# WX0_011_910DL.net
KiCad netlist of a schematic drawn in Altium Designer
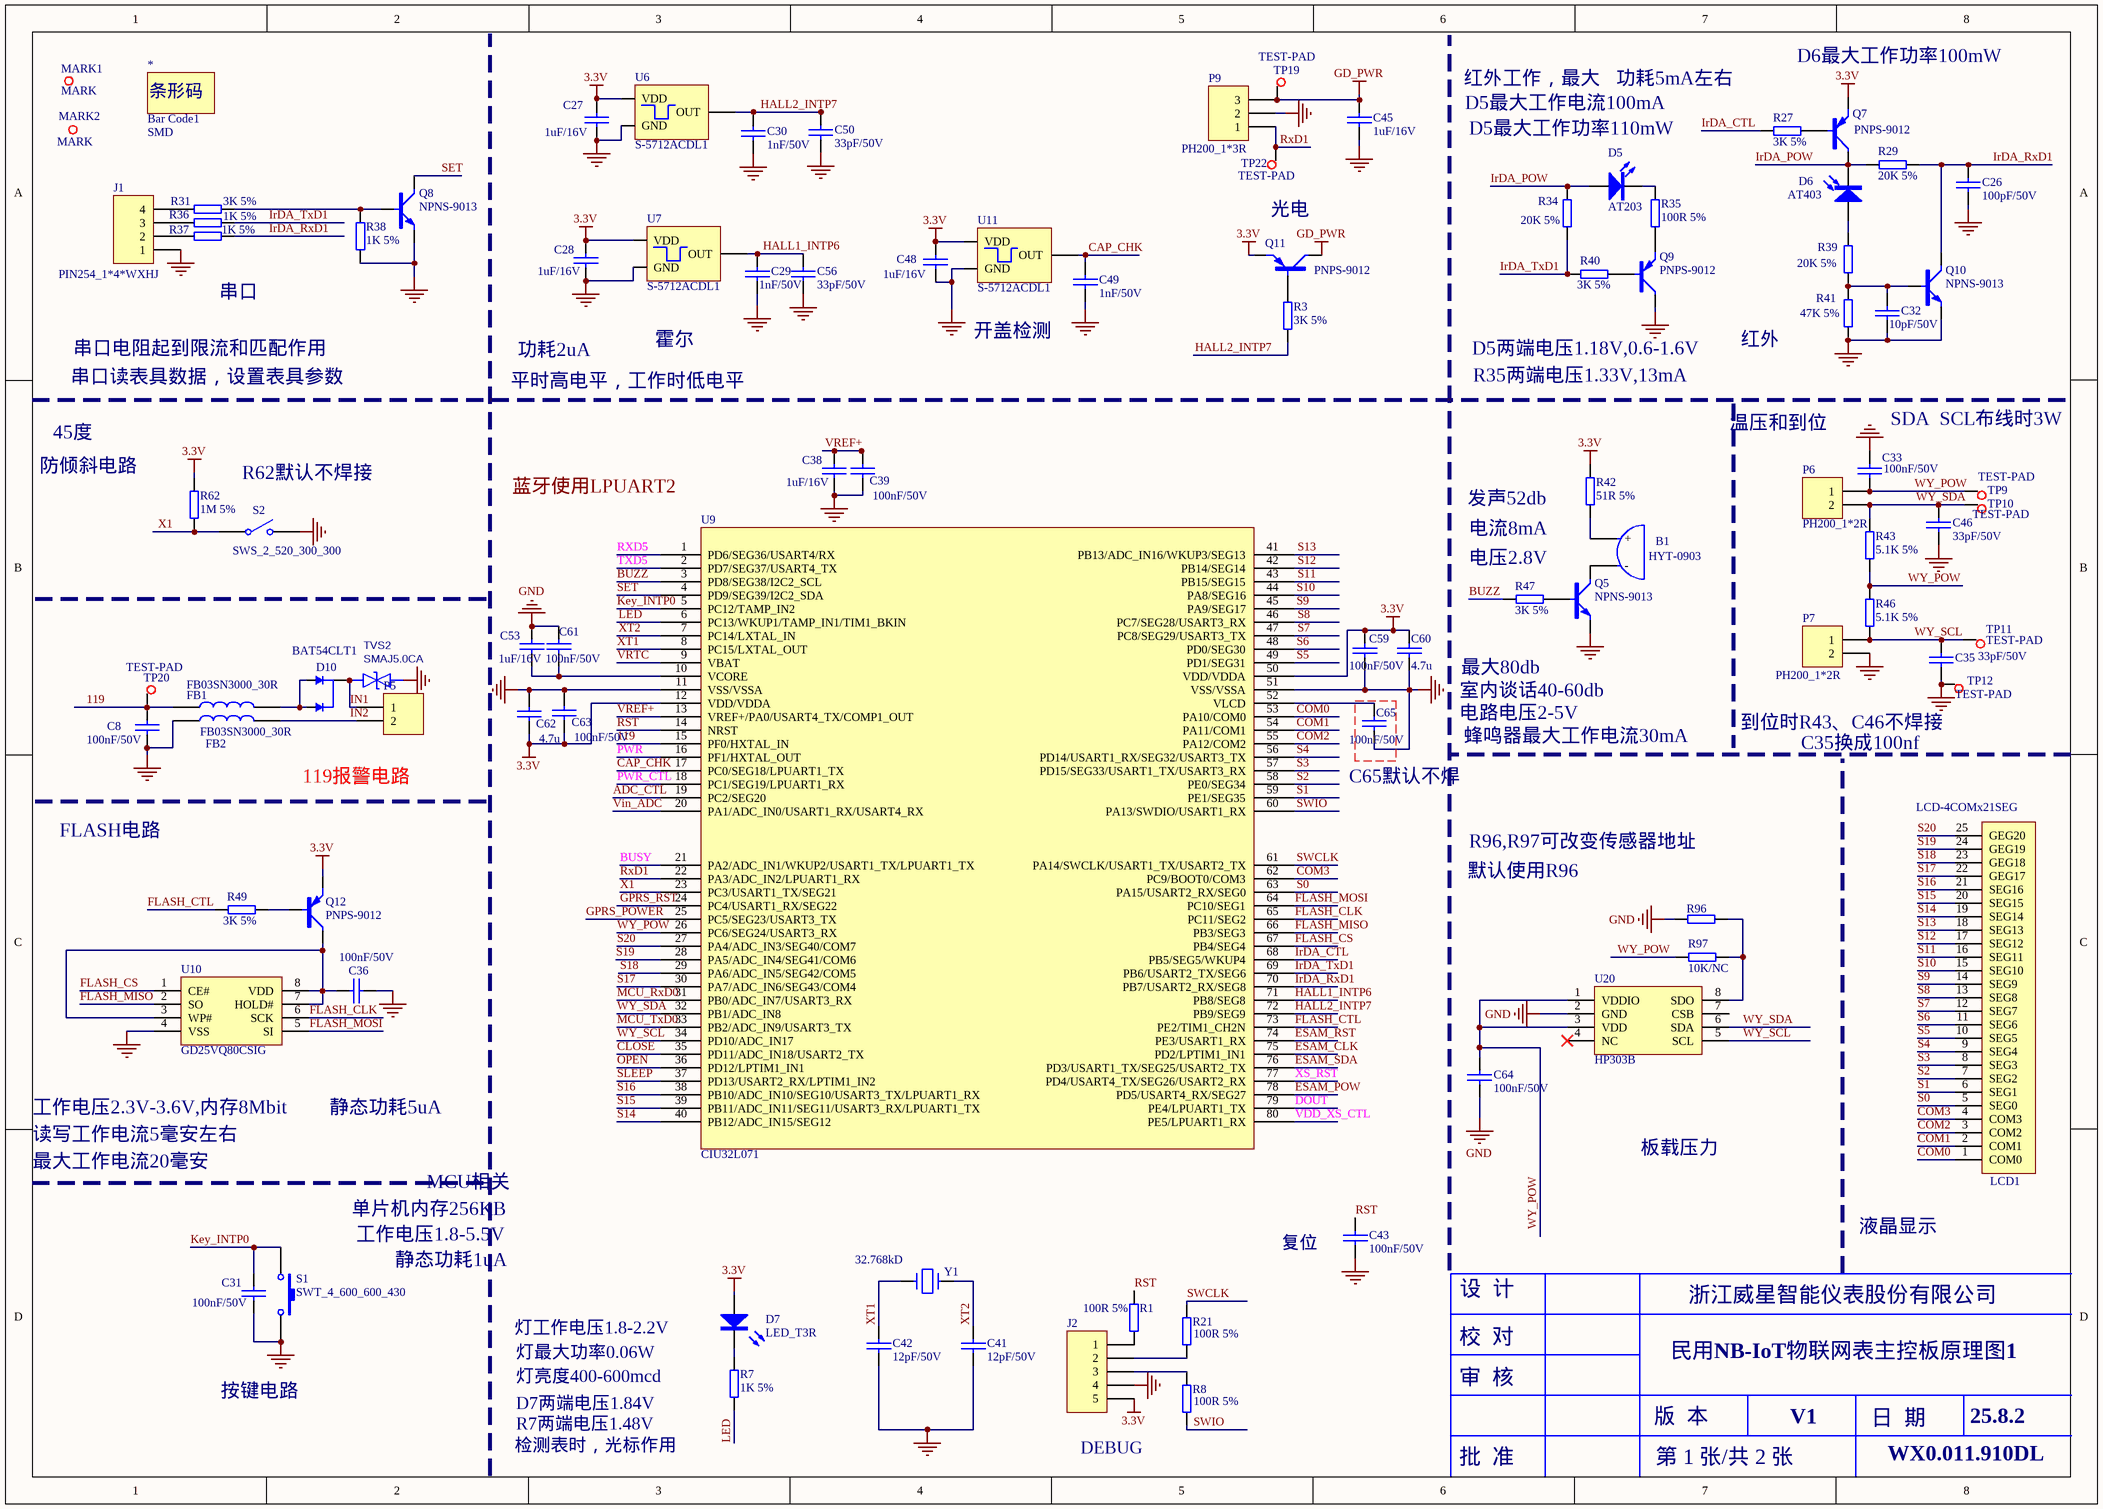
[diagram p0: WX0.011.910DL.SchDoc]

(export (version "E")
  (design (tool "Eeschema 10.0.6"))
  (components
    (comp (ref "*")
      (value "Bar Code1")
      (footprint "Bar Code1")
      (description "条形码 ,填充，无需焊接器件")
      (fields (field (name "PART NUMBER") "AD_WXHJ_Bar Code_02") (field (name "SMD/DIP") "SMD"))
      (libsource (lib "Database_Libs2") (part "05_AD_WXHJ_Bar Code_02"))
    )
    (comp (ref "B1")
      (value "HYT-0903")
      (footprint "HYT-0903")
      (description "直插,直径9mm,高5.5mm,5 V,2 V,30 mA,兴化市华宇电子有限公司,HYT-0903")
      (fields (field (name "PART NUMBER") "1010602-0007"))
      (libsource (lib "Database_Libs2") (part "07_HYT-0903"))
    )
    (comp (ref "C8")
      (value "100nF/50V")
      (footprint "CAP0603")
      (description "104pF,50 V,±10%,0603,国巨,CC0603KRX7R9BB104")
      (fields (field (name "PART NUMBER") "101020103-0021"))
      (libsource (lib "Database_Libs2") (part "CC03K7R9_100N"))
    )
    (comp (ref "C26")
      (value "100pF/50V")
      (footprint "CAP0603")
      (description "101pf,50 V,±5%,0603,国巨,CC0603JRNP09BN101")
      (fields (field (name "PART NUMBER") "101020103-0010"))
      (libsource (lib "Database_Libs2") (part "CC03JPO9_101P"))
    )
    (comp (ref "C27")
      (value "1uF/16V")
      (footprint "CAP0603")
      (description "105pF,16 V,±10%,0603,国巨,CC0603KRX7R7BB105")
      (fields (field (name "PART NUMBER") "101020103-0003"))
      (libsource (lib "Database_Libs2") (part "CC03K7R7_1U"))
    )
    (comp (ref "C28")
      (value "1uF/16V")
      (footprint "CAP0603")
      (description "105pF,16 V,±10%,0603,国巨,CC0603KRX7R7BB105")
      (fields (field (name "PART NUMBER") "101020103-0003"))
      (libsource (lib "Database_Libs2") (part "CC03K7R7_1U"))
    )
    (comp (ref "C29")
      (value "1nF/50V")
      (footprint "CAP0603")
      (description "102pF,50 V,±10%,0603,国巨,CC0603KRX7R9BB102")
      (fields (field (name "PART NUMBER") "101020103-0022"))
      (libsource (lib "Database_Libs2") (part "CC03K7R9_1N"))
    )
    (comp (ref "C30")
      (value "1nF/50V")
      (footprint "CAP0603")
      (description "102pF,50 V,±10%,0603,国巨,CC0603KRX7R9BB102")
      (fields (field (name "PART NUMBER") "101020103-0022"))
      (libsource (lib "Database_Libs2") (part "CC03K7R9_1N"))
    )
    (comp (ref "C31")
      (value "100nF/50V")
      (footprint "CAP0603")
      (description "104pF,50 V,±10%,0603,国巨,CC0603KRX7R9BB104")
      (fields (field (name "PART NUMBER") "101020103-0021"))
      (libsource (lib "Database_Libs2") (part "CC03K7R9_100N"))
    )
    (comp (ref "C32")
      (value "10pF/50V")
      (footprint "CAP0603")
      (description "10pF,50 V,±5%,0603,X7R,国巨,CC0603JRNPO9BN100")
      (fields (field (name "PART NUMBER") "101020103-0014"))
      (libsource (lib "Database_Libs2") (part "CC03JPO9_10P"))
    )
    (comp (ref "C33")
      (value "100nF/50V")
      (footprint "CAP0603")
      (description "104pF,50 V,±10%,0603,国巨,CC0603KRX7R9BB104")
      (fields (field (name "PART NUMBER") "101020103-0021"))
      (libsource (lib "Database_Libs2") (part "CC03K7R9_100N"))
    )
    (comp (ref "C35")
      (value "33pF/50V")
      (footprint "CAP0603")
      (fields (field (name "PART NUMBER") "101020103-0021"))
      (libsource (lib "Database_Libs2") (part "CC03K7R9_100N"))
    )
    (comp (ref "C36")
      (value "100nF/50V")
      (footprint "CAP0603")
      (description "104pF,50 V,±10%,0603,国巨,CC0603KRX7R9BB104")
      (fields (field (name "PART NUMBER") "101020103-0021"))
      (libsource (lib "Database_Libs2") (part "CC03K7R9_100N"))
    )
    (comp (ref "C38")
      (value "1uF/16V")
      (footprint "CAP0603")
      (description "105pF,16 V,±10%,0603,国巨,CC0603KRX7R7BB105")
      (fields (field (name "PART NUMBER") "101020103-0003"))
      (libsource (lib "Database_Libs2") (part "CC03K7R7_1U"))
    )
    (comp (ref "C39")
      (value "100nF/50V")
      (footprint "CAP0603")
      (description "104pF,50 V,±10%,0603,国巨,CC0603KRX7R9BB104")
      (fields (field (name "PART NUMBER") "101020103-0021"))
      (libsource (lib "Database_Libs2") (part "CC03K7R9_100N"))
    )
    (comp (ref "C41")
      (value "12pF/50V")
      (footprint "CAP0603")
      (description "12P,50 V,±5%,0603,国巨,CC0603JRNPO9BN12")
      (fields (field (name "PART NUMBER") "101020103-0005"))
      (libsource (lib "Database_Libs2") (part "CC03JPO9_12P"))
    )
    (comp (ref "C42")
      (value "12pF/50V")
      (footprint "CAP0603")
      (description "12P,50 V,±5%,0603,国巨,CC0603JRNPO9BN12")
      (fields (field (name "PART NUMBER") "101020103-0005"))
      (libsource (lib "Database_Libs2") (part "CC03JPO9_12P"))
    )
    (comp (ref "C43")
      (value "100nF/50V")
      (footprint "CAP0603")
      (description "104pF,50 V,±10%,0603,国巨,CC0603KRX7R9BB104")
      (fields (field (name "PART NUMBER") "101020103-0021"))
      (libsource (lib "Database_Libs2") (part "CC03K7R9_100N"))
    )
    (comp (ref "C45")
      (value "1uF/16V")
      (footprint "CAP0603")
      (description "105pF,16 V,±10%,0603,国巨,CC0603KRX7R7BB105")
      (fields (field (name "PART NUMBER") "101020103-0003"))
      (libsource (lib "Database_Libs2") (part "CC03K7R7_1U"))
    )
    (comp (ref "C46")
      (value "33pF/50V")
      (footprint "CAP0603")
      (description "33pF,50 V,±10%,0603,国巨,CC0603KRNPO9BN33")
      (fields (field (name "PART NUMBER") "101020103-0027"))
      (libsource (lib "Database_Libs2") (part "CC03KPO9_33P"))
    )
    (comp (ref "C48")
      (value "1uF/16V")
      (footprint "CAP0603")
      (description "105pF,16 V,±10%,0603,国巨,CC0603KRX7R7BB105")
      (fields (field (name "PART NUMBER") "101020103-0003"))
      (libsource (lib "Database_Libs2") (part "CC03K7R7_1U"))
    )
    (comp (ref "C49")
      (value "1nF/50V")
      (footprint "CAP0603")
      (description "102pF,50 V,±10%,0603,国巨,CC0603KRX7R9BB102")
      (fields (field (name "PART NUMBER") "101020103-0022"))
      (libsource (lib "Database_Libs2") (part "CC03K7R9_1N"))
    )
    (comp (ref "C50")
      (value "33pF/50V")
      (footprint "CAP0603")
      (description "33pF,50 V,±10%,0603,国巨,CC0603KRNPO9BN33")
      (fields (field (name "PART NUMBER") "101020103-0027"))
      (libsource (lib "Database_Libs2") (part "CC03KPO9_33P"))
    )
    (comp (ref "C53")
      (value "1uF/16V")
      (footprint "CAP0603")
      (description "105pF,16 V,±10%,0603,国巨,CC0603KRX7R7BB105")
      (fields (field (name "PART NUMBER") "101020103-0003"))
      (libsource (lib "Database_Libs2") (part "CC03K7R7_1U"))
    )
    (comp (ref "C56")
      (value "33pF/50V")
      (footprint "CAP0603")
      (description "33pF,50 V,±10%,0603,国巨,CC0603KRNPO9BN33")
      (fields (field (name "PART NUMBER") "101020103-0027"))
      (libsource (lib "Database_Libs2") (part "CC03KPO9_33P"))
    )
    (comp (ref "C59")
      (value "100nF/50V")
      (footprint "CAP0603")
      (description "104pF,50 V,±10%,0603,国巨,CC0603KRX7R9BB104")
      (fields (field (name "PART NUMBER") "101020103-0021"))
      (libsource (lib "Database_Libs2") (part "CC03K7R9_100N"))
    )
    (comp (ref "C60")
      (value "4.7u")
      (footprint "CAP0603")
      (description "104pF,50 V,±10%,0603,国巨,CC0603KRX7R9BB104")
      (fields (field (name "PART NUMBER") "101020103-0021"))
      (libsource (lib "Database_Libs2") (part "CC03K7R9_100N"))
    )
    (comp (ref "C61")
      (value "100nF/50V")
      (footprint "CAP0603")
      (description "104pF,50 V,±10%,0603,国巨,CC0603KRX7R9BB104")
      (fields (field (name "PART NUMBER") "101020103-0021"))
      (libsource (lib "Database_Libs2") (part "CC03K7R9_100N"))
    )
    (comp (ref "C62")
      (value "4.7u")
      (footprint "CAP0603")
      (description "104pF,50 V,±10%,0603,国巨,CC0603KRX7R9BB104")
      (fields (field (name "PART NUMBER") "101020103-0021"))
      (libsource (lib "Database_Libs2") (part "CC03K7R9_100N"))
    )
    (comp (ref "C63")
      (value "100nF/50V")
      (footprint "CAP0603")
      (description "104pF,50 V,±10%,0603,国巨,CC0603KRX7R9BB104")
      (fields (field (name "PART NUMBER") "101020103-0021"))
      (libsource (lib "Database_Libs2") (part "CC03K7R9_100N"))
    )
    (comp (ref "C64")
      (value "100nF/50V")
      (footprint "CAP0603")
      (description "104pF,50 V,±10%,0603,国巨,CC0603KRX7R9BB104")
      (fields (field (name "PART NUMBER") "101020103-0021"))
      (libsource (lib "Database_Libs2") (part "CC03K7R9_100N"))
    )
    (comp (ref "C65")
      (value "100nF/50V")
      (footprint "CAP0603")
      (description "104pF,50 V,±10%,0603,国巨,CC0603KRX7R9BB104")
      (fields (field (name "PART NUMBER") "101020103-0021"))
      (libsource (lib "Database_Libs2") (part "CC03K7R9_100N"))
    )
    (comp (ref "D5")
      (value "AT203")
      (footprint "IR_254_532_300")
      (description "DIP-2,φ3,插件,红光,上海品观电子有限公司/可得,AT203")
      (fields (field (name "PART NUMBER") "101040102-0010"))
      (libsource (lib "Database_Libs2") (part "01_AT203"))
    )
    (comp (ref "D6")
      (value "AT403")
      (footprint "IR_254_532_300")
      (description "DIP-2,φ3,插件,红光,上海品观电子有限公司/可得,AT403-PD-01")
      (fields (field (name "PART NUMBER") "101040102-0011"))
      (libsource (lib "Database_Libs2") (part "01_AT403"))
    )
    (comp (ref "D7")
      (value "LED_T3R")
      (footprint "LED2_300")
      (description "圆形插件,3mm 圆形,插件,红光,湖北匡通电子有限公司,3BB4HC")
      (fields (field (name "PART NUMBER") "101040102-0001"))
      (libsource (lib "Database_Libs2") (part "01-LED_T3R"))
    )
    (comp (ref "D10")
      (value "BAT54CLT1")
      (footprint "SOT-23")
      (description "BAT54CLT1，SOT23-3,SOT23-3,0.2 A,0.8 V,30 V,安森美,BAT54CLT1")
      (fields (field (name "PART NUMBER") "101040101-0038"))
      (libsource (lib "Database_Libs2") (part "02_BAT54CLT1"))
    )
    (comp (ref "FB1")
      (value "FB03SN3000_30R")
      (footprint "IND0603")
      (description "chilisin(奇力新),0603,30Ω ±25% @100MHz,150 V,125 ℃,PBY160808T-300Y-N,-55 ℃,不含铅,,,圆盘,30Ω ±25% @100MHz")
      (fields (field (name "PART NUMBER") "109010101-0003"))
      (libsource (lib "Database_Libs2") (part "06_FB03SN3000_30R"))
    )
    (comp (ref "FB2")
      (value "FB03SN3000_30R")
      (footprint "IND0603")
      (description "chilisin(奇力新),0603,30Ω ±25% @100MHz,150 V,125 ℃,PBY160808T-300Y-N,-55 ℃,不含铅,,,圆盘,30Ω ±25% @100MHz")
      (fields (field (name "PART NUMBER") "109010101-0003"))
      (libsource (lib "Database_Libs2") (part "06_FB03SN3000_30R"))
    )
    (comp (ref "J1")
      (value "PIN254_1*4*WXHJ")
      (footprint "PIN254_1*4*WXHJ")
      (description "1*4 ，Φ1.0 ，2.54mm，直脚,无需焊接器件")
      (fields (field (name "PART NUMBER") "AD_WXHJ_PinHeader_01"))
      (libsource (lib "Database_Libs2") (part "PIN254_1*4*WXHJ"))
    )
    (comp (ref "J2")
      (value "PIN254_1*5*WXHJ")
      (footprint "PIN254_1*5*1100S")
      (description "1*5 ，Φ1.0 ，2.54mm，直脚,无需焊接器件")
      (fields (field (name "PART NUMBER") "AD_WXHJ_PinHeader_02"))
      (libsource (lib "Database_Libs2") (part "PIN254_1*5*WXHJ"))
    )
    (comp (ref "LCD1")
      (value "GVH21861A-HPP")
      (footprint "LCD_GVH21861A-HPP")
      (fields (field (name "PART NUMBER") "1010801-0028") (field (name "SMD/DIP") "LCD-4COMx21SEG"))
      (libsource (lib "Database_Libs2") (part "03_LCD_GVH21861A-HPP"))
    )
    (comp (ref "MARK1")
      (value "MARK")
      (footprint "MARK")
      (description "MARK点")
      (fields (field (name "PART NUMBER") "AD_WXHJ_MARK_01"))
      (libsource (lib "Database_Libs2") (part "MARK"))
    )
    (comp (ref "MARK2")
      (value "MARK")
      (footprint "MARK")
      (description "MARK点")
      (fields (field (name "PART NUMBER") "AD_WXHJ_MARK_01"))
      (libsource (lib "Database_Libs2") (part "MARK"))
    )
    (comp (ref "P5")
      (value "~")
      (footprint "WXHJ_Connect_01")
      (description "电源连接线")
      (fields (field (name "PART NUMBER") "AD_WXHJ_Connect_01"))
      (libsource (lib "Database_Libs2") (part "WXHJ_Connect_01"))
    )
    (comp (ref "P6")
      (value "PH200_1*2R")
      (footprint "PH200_1*2R")
      (description "2.0-2AW,直插弯座，2PIN，脚间距2mm，带防翘起,公头,单排,2.0-2AW;直插弯座，2PIN,脚间距2mm，带防翘起")
      (fields (field (name "PART NUMBER") "1010902-0105"))
      (libsource (lib "Database_Libs2") (part "PH200_1*2R"))
    )
    (comp (ref "P7")
      (value "PH200_1*2R")
      (footprint "PH200_1*2R")
      (description "2.0-2AW,直插弯座，2PIN，脚间距2mm，带防翘起,公头,单排,2.0-2AW;直插弯座，2PIN,脚间距2mm，带防翘起")
      (fields (field (name "PART NUMBER") "1010902-0105"))
      (libsource (lib "Database_Libs2") (part "PH200_1*2R"))
    )
    (comp (ref "P9")
      (value "PH200_1*3R")
      (footprint "PH200_1*3R")
      (description "2.0-3AW,3PIN，2mm脚间距,公头,单排,2.0-3AW；3PIN，脚间距2mm直插弯座带防翘起")
      (fields (field (name "PART NUMBER") "1010902-0104"))
      (libsource (lib "Database_Libs2") (part "PH200_1*3R"))
    )
    (comp (ref "Q5")
      (value "NPNS-9013")
      (footprint "SOT-23")
      (description "9013,NPN,SOT-23,长电,S9013")
      (fields (field (name "PART NUMBER") "101040201-0002"))
      (libsource (lib "Database_Libs2") (part "03_NPNS-9013"))
    )
    (comp (ref "Q7")
      (value "PNPS-9012")
      (footprint "SOT-23")
      (description "9012,PNP,SOT-23,JCET;长电,S9012")
      (fields (field (name "PART NUMBER") "101040201-0001"))
      (libsource (lib "Database_Libs2") (part "03_PNPS-9012"))
    )
    (comp (ref "Q8")
      (value "NPNS-9013")
      (footprint "SOT-23")
      (description "9013,NPN,SOT-23,长电,S9013")
      (fields (field (name "PART NUMBER") "101040201-0002"))
      (libsource (lib "Database_Libs2") (part "03_NPNS-9013"))
    )
    (comp (ref "Q9")
      (value "PNPS-9012")
      (footprint "SOT-23")
      (description "9012,PNP,SOT-23,JCET;长电,S9012")
      (fields (field (name "PART NUMBER") "101040201-0001"))
      (libsource (lib "Database_Libs2") (part "03_PNPS-9012"))
    )
    (comp (ref "Q10")
      (value "NPNS-9013")
      (footprint "SOT-23")
      (description "9013,NPN,SOT-23,长电,S9013")
      (fields (field (name "PART NUMBER") "101040201-0002"))
      (libsource (lib "Database_Libs2") (part "03_NPNS-9013"))
    )
    (comp (ref "Q11")
      (value "PNPS-9012")
      (footprint "SOT-23")
      (description "9012,PNP,SOT-23,JCET;长电,S9012")
      (fields (field (name "PART NUMBER") "101040201-0001"))
      (libsource (lib "Database_Libs2") (part "03_PNPS-9012"))
    )
    (comp (ref "Q12")
      (value "PNPS-9012")
      (footprint "SOT-23")
      (description "9012,PNP,SOT-23,JCET;长电,S9012")
      (fields (field (name "PART NUMBER") "101040201-0001"))
      (libsource (lib "Database_Libs2") (part "03_PNPS-9012"))
    )
    (comp (ref "R1")
      (value "100R 5%")
      (footprint "RES0603")
      (description "100R,±5%,1/10W,0603,国巨,RC0603JR-07100RL")
      (fields (field (name "PART NUMBER") "101010103-0022"))
      (libsource (lib "Database_Libs2") (part "RC03J_100R"))
    )
    (comp (ref "R3")
      (value "3K 5%")
      (footprint "RES0603")
      (description "国巨,±5%,0603,,155 ℃,-55 ℃,RC0603JR-073KL,无铅,100 ppm/℃,1/10W,,3K")
      (fields (field (name "PART NUMBER") "101010103-0006"))
      (libsource (lib "Database_Libs2") (part "RC03J_3K"))
    )
    (comp (ref "R7")
      (value "1K 5%")
      (footprint "RES0603")
      (description "1K,±5%,1/10W,0603,国巨,RC0603JR-071KL")
      (fields (field (name "PART NUMBER") "101010103-0008"))
      (libsource (lib "Database_Libs2") (part "RC03J_1K"))
    )
    (comp (ref "R8")
      (value "100R 5%")
      (footprint "RES0603")
      (description "100R,±5%,1/10W,0603,国巨,RC0603JR-07100RL")
      (fields (field (name "PART NUMBER") "101010103-0022"))
      (libsource (lib "Database_Libs2") (part "RC03J_100R"))
    )
    (comp (ref "R21")
      (value "100R 5%")
      (footprint "RES0603")
      (description "100R,±5%,1/10W,0603,国巨,RC0603JR-07100RL")
      (fields (field (name "PART NUMBER") "101010103-0022"))
      (libsource (lib "Database_Libs2") (part "RC03J_100R"))
    )
    (comp (ref "R27")
      (value "3K 5%")
      (footprint "RES0603")
      (description "国巨,±5%,0603,,155 ℃,-55 ℃,RC0603JR-073KL,无铅,100 ppm/℃,1/10W,,3K")
      (fields (field (name "PART NUMBER") "101010103-0006"))
      (libsource (lib "Database_Libs2") (part "RC03J_3K"))
    )
    (comp (ref "R29")
      (value "20K 5%")
      (footprint "RES0603")
      (description "国巨,±5%,0603,,155 ℃,-55 ℃,RC0603JR-0720KL,无铅,200 ppm/℃,1/10W,,20K")
      (fields (field (name "PART NUMBER") "101010103-0004"))
      (libsource (lib "Database_Libs2") (part "RC03J_20K"))
    )
    (comp (ref "R31")
      (value "3K 5%")
      (footprint "RES0603")
      (description "国巨,±5%,0603,,155 ℃,-55 ℃,RC0603JR-073KL,无铅,100 ppm/℃,1/10W,,3K")
      (fields (field (name "PART NUMBER") "101010103-0006"))
      (libsource (lib "Database_Libs2") (part "RC03J_3K"))
    )
    (comp (ref "R34")
      (value "20K 5%")
      (footprint "RES0603")
      (description "国巨,±5%,0603,,155 ℃,-55 ℃,RC0603JR-0720KL,无铅,200 ppm/℃,1/10W,,20K")
      (fields (field (name "PART NUMBER") "101010103-0004"))
      (libsource (lib "Database_Libs2") (part "RC03J_20K"))
    )
    (comp (ref "R35")
      (value "100R 5%")
      (footprint "RES0603")
      (description "100R,±5%,1/10W,0603,国巨,RC0603JR-07100RL")
      (fields (field (name "PART NUMBER") "101010103-0022"))
      (libsource (lib "Database_Libs2") (part "RC03J_100R"))
    )
    (comp (ref "R36")
      (value "1K 5%")
      (footprint "RES0603")
      (description "1K,±5%,1/10W,0603,国巨,RC0603JR-071KL")
      (fields (field (name "PART NUMBER") "101010103-0008"))
      (libsource (lib "Database_Libs2") (part "RC03J_1K"))
    )
    (comp (ref "R37")
      (value "1K 5%")
      (footprint "RES0603")
      (description "1K,±5%,1/10W,0603,国巨,RC0603JR-071KL")
      (fields (field (name "PART NUMBER") "101010103-0008"))
      (libsource (lib "Database_Libs2") (part "RC03J_1K"))
    )
    (comp (ref "R38")
      (value "1K 5%")
      (footprint "RES0603")
      (description "1K,±5%,1/10W,0603,国巨,RC0603JR-071KL")
      (fields (field (name "PART NUMBER") "101010103-0008"))
      (libsource (lib "Database_Libs2") (part "RC03J_1K"))
    )
    (comp (ref "R39")
      (value "20K 5%")
      (footprint "RES0603")
      (description "国巨,±5%,0603,,155 ℃,-55 ℃,RC0603JR-0720KL,无铅,200 ppm/℃,1/10W,,20K")
      (fields (field (name "PART NUMBER") "101010103-0004"))
      (libsource (lib "Database_Libs2") (part "RC03J_20K"))
    )
    (comp (ref "R40")
      (value "3K 5%")
      (footprint "RES0603")
      (description "国巨,±5%,0603,,155 ℃,-55 ℃,RC0603JR-073KL,无铅,100 ppm/℃,1/10W,,3K")
      (fields (field (name "PART NUMBER") "101010103-0006"))
      (libsource (lib "Database_Libs2") (part "RC03J_3K"))
    )
    (comp (ref "R41")
      (value "47K 5%")
      (footprint "RES0603")
      (description "47K,±5%,1/10W,0603,国巨,RC0603JR-0747KL")
      (fields (field (name "PART NUMBER") "101010103-0012"))
      (libsource (lib "Database_Libs2") (part "RC03J_47K"))
    )
    (comp (ref "R42")
      (value "51R 5%")
      (footprint "RES0603")
      (description "国巨,±5%,0603,,155 ℃,-55 ℃,RC0603JR-0751RL,无铅,100 ppm/℃,1/10W,,51欧")
      (fields (field (name "PART NUMBER") "101010103-0037"))
      (libsource (lib "Database_Libs2") (part "RC03J_51R"))
    )
    (comp (ref "R43")
      (value "5.1K 5%")
      (footprint "RES0603")
      (description "国巨,±5%,0603,,155 ℃,55 ℃,RC0603JR-075.1KL,无铅,200 ppm/℃,1/10W,,5.1k")
      (fields (field (name "PART NUMBER") "101010103-0015"))
      (libsource (lib "Database_Libs2") (part "RC03J_5.1K"))
    )
    (comp (ref "R46")
      (value "5.1K 5%")
      (footprint "RES0603")
      (description "国巨,±5%,0603,,155 ℃,55 ℃,RC0603JR-075.1KL,无铅,200 ppm/℃,1/10W,,5.1k")
      (fields (field (name "PART NUMBER") "101010103-0015"))
      (libsource (lib "Database_Libs2") (part "RC03J_5.1K"))
    )
    (comp (ref "R47")
      (value "3K 5%")
      (footprint "RES0603")
      (description "国巨,±5%,0603,,155 ℃,-55 ℃,RC0603JR-073KL,无铅,100 ppm/℃,1/10W,,3K")
      (fields (field (name "PART NUMBER") "101010103-0006"))
      (libsource (lib "Database_Libs2") (part "RC03J_3K"))
    )
    (comp (ref "R49")
      (value "3K 5%")
      (footprint "RES0603")
      (description "国巨,±5%,0603,,155 ℃,-55 ℃,RC0603JR-073KL,无铅,100 ppm/℃,1/10W,,3K")
      (fields (field (name "PART NUMBER") "101010103-0006"))
      (libsource (lib "Database_Libs2") (part "RC03J_3K"))
    )
    (comp (ref "R62")
      (value "1M 5%")
      (footprint "RES0603")
      (description "国巨,±5%,0603,,155 ℃,-55 ℃,RC0603JR-071ML,无铅,200 ppm/℃,1/10W,,1M")
      (fields (field (name "PART NUMBER") "101010103-0002"))
      (libsource (lib "Database_Libs2") (part "RC03J_1M"))
    )
    (comp (ref "R96")
      (value "0R 5%")
      (footprint "RES0603")
      (description "国巨,±5%,0603,,155 ℃,-55 ℃,RC0603J2-070RL,无铅,200 ppm/℃,1/10W,,0R")
      (fields (field (name "PART NUMBER") "101010103-0001"))
      (libsource (lib "Database_Libs2") (part "RC03J_0R"))
    )
    (comp (ref "R97")
      (value "10K/NC")
      (footprint "RES0603")
      (description "国巨,±5%,0603,,155 ℃,-55 ℃,RC0603JR-071ML,无铅,200 ppm/℃,1/10W,,1M")
      (libsource (lib "Database_Libs2") (part "RC03J_1M"))
    )
    (comp (ref "S1")
      (value "SWT_4_600_600_430")
      (footprint "SWT_4_600_600")
      (description "TS-1102,机械轻触,6*6*4.3直插,6*6*4.3直插,乐清市羽欧电子")
      (fields (field (name "PART NUMBER") "1011001-0027"))
      (libsource (lib "Database_Libs2") (part "07_SWT_4_600_600_430"))
    )
    (comp (ref "S2")
      (value "SWS_2_520_300_300")
      (footprint "SWS_2_520_300")
      (description "CSX-SEN-645B,垂直45°开关转换,3*5.2mm,360°任意方位倾斜检测,深圳市成晟科技有限公司")
      (fields (field (name "PART NUMBER") "1011001-0051"))
      (libsource (lib "Database_Libs2") (part "07_SWS_2_520_300_300"))
    )
    (comp (ref "TP9")
      (value "TEST-PAD")
      (footprint "TEST-PAD")
      (description "单面焊盘测试点")
      (fields (field (name "PART NUMBER") "AD_WXHJ_TEST-PAD_01"))
      (libsource (lib "Database_Libs2") (part "TEST-PAD"))
    )
    (comp (ref "TP10")
      (value "TEST-PAD")
      (footprint "TEST-PAD")
      (description "单面焊盘测试点")
      (fields (field (name "PART NUMBER") "AD_WXHJ_TEST-PAD_01"))
      (libsource (lib "Database_Libs2") (part "TEST-PAD"))
    )
    (comp (ref "TP11")
      (value "TEST-PAD")
      (footprint "TEST-PAD")
      (description "单面焊盘测试点")
      (fields (field (name "PART NUMBER") "AD_WXHJ_TEST-PAD_01"))
      (libsource (lib "Database_Libs2") (part "TEST-PAD"))
    )
    (comp (ref "TP12")
      (value "TEST-PAD")
      (footprint "TEST-PAD")
      (description "单面焊盘测试点")
      (fields (field (name "PART NUMBER") "AD_WXHJ_TEST-PAD_01"))
      (libsource (lib "Database_Libs2") (part "TEST-PAD"))
    )
    (comp (ref "TP19")
      (value "TEST-PAD")
      (footprint "TEST-PAD")
      (description "单面焊盘测试点")
      (fields (field (name "PART NUMBER") "AD_WXHJ_TEST-PAD_01"))
      (libsource (lib "Database_Libs2") (part "TEST-PAD"))
    )
    (comp (ref "TP20")
      (value "TEST-PAD")
      (footprint "TEST-PAD")
      (description "单面焊盘测试点")
      (fields (field (name "PART NUMBER") "AD_WXHJ_TEST-PAD_01"))
      (libsource (lib "Database_Libs2") (part "TEST-PAD"))
    )
    (comp (ref "TP22")
      (value "TEST-PAD")
      (footprint "TEST-PAD")
      (description "单面焊盘测试点")
      (fields (field (name "PART NUMBER") "AD_WXHJ_TEST-PAD_01"))
      (libsource (lib "Database_Libs2") (part "TEST-PAD"))
    )
    (comp (ref "TVS2")
      (value "SMAJ5.0CA")
      (footprint "SMAJ5.0CA")
      (fields (field (name "BOM_SUPPLIER PART") "C693487") (field (name "CONTRIBUTOR") "LCSC"))
      (libsource (lib "Discrete_WX") (part "SMAJ5.0CA_C693487"))
    )
    (comp (ref "U6")
      (value "S-5712ACDL1")
      (footprint "SOT-23")
      (description "S-5712ACDL1,SOT23-3,3.5 V,1.6 V,2 uA,精工电子,S-5712ACDL1")
      (fields (field (name "PART NUMBER") "1010504-0002"))
      (libsource (lib "Database_Libs2") (part "01_S-5712ACDL1"))
    )
    (comp (ref "U7")
      (value "S-5712ACDL1")
      (footprint "SOT-23")
      (description "S-5712ACDL1,SOT23-3,3.5 V,1.6 V,2 uA,精工电子,S-5712ACDL1")
      (fields (field (name "PART NUMBER") "1010504-0002"))
      (libsource (lib "Database_Libs2") (part "01_S-5712ACDL1"))
    )
    (comp (ref "U9") (value "CIU32L071") (libsource (lib "1111") (part "CIU32L061")))
    (comp (ref "U10") (value "GD25VQ80CSIG") (libsource (lib "Chip_WX") (part "04_GD25VQ80CSIG")))
    (comp (ref "U11")
      (value "S-5712ACDL1")
      (footprint "SOT-23")
      (description "S-5712ACDL1,SOT23-3,3.5 V,1.6 V,2 uA,精工电子,S-5712ACDL1")
      (fields (field (name "PART NUMBER") "1010504-0002"))
      (libsource (lib "Database_Libs2") (part "01_S-5712ACDL1"))
    )
    (comp (ref "U20")
      (value "HP303B")
      (footprint "LGA_8")
      (fields (field (name "PART NUMBER") "1011301-0022"))
      (libsource (lib "Schlib2") (part "HP303B"))
    )
    (comp (ref "Y1")
      (value "32.768kD")
      (footprint "SMD-3215_2P")
      (fields (field (name "PART NUMBER") "1010601-0020"))
      (libsource (lib "Database_Libs2") (part "04_XTALSG12MD_32.768kD"))
    )
  )
  (nets
    (net (code "1") (name "/119") (class "Default")
      (node (ref "C8") (pin "1") (pinfunction "1_1") (pintype "passive"))
      (node (ref "FB1") (pin "1") (pinfunction "1_1") (pintype "passive"))
      (node (ref "TP20") (pin "1") (pinfunction "1_1") (pintype "passive"))
      (node (ref "U9") (pin "15") (pinfunction "PF0/HXTAL_IN_15") (pintype "passive"))
    )
    (net (code "2") (name "/ADC_CTL") (class "Default")
      (node (ref "U9") (pin "19") (pinfunction "PC2/SEG20_19") (pintype "passive"))
    )
    (net (code "3") (name "/BUSY") (class "Default")
      (node (ref "U9") (pin "21") (pinfunction "PA2/ADC_IN1/WKUP2/USART1_TX/LPUART1_TX_21") (pintype "passive"))
    )
    (net (code "4") (name "/BUZZ") (class "Default")
      (node (ref "R47") (pin "1") (pinfunction "1_1") (pintype "passive"))
      (node (ref "U9") (pin "3") (pinfunction "PD8/SEG38/I2C2_SCL_3") (pintype "passive"))
    )
    (net (code "5") (name "/CAP_CHK") (class "Default")
      (node (ref "C49") (pin "1") (pinfunction "1_1") (pintype "passive"))
      (node (ref "U11") (pin "2") (pinfunction "OUT_2") (pintype "passive"))
      (node (ref "U9") (pin "17") (pinfunction "PC0/SEG18/LPUART1_TX_17") (pintype "passive"))
    )
    (net (code "6") (name "/CLOSE") (class "Default")
      (node (ref "U9") (pin "35") (pinfunction "PD11/ADC_IN18/USART2_TX_35") (pintype "passive"))
    )
    (net (code "7") (name "/COM0") (class "Default")
      (node (ref "LCD1") (pin "1") (pinfunction "COM0_1") (pintype "passive"))
      (node (ref "U9") (pin "53") (pinfunction "PA10/COM0_53") (pintype "passive"))
    )
    (net (code "8") (name "/COM1") (class "Default")
      (node (ref "LCD1") (pin "2") (pinfunction "COM1_2") (pintype "passive"))
      (node (ref "U9") (pin "54") (pinfunction "PA11/COM1_54") (pintype "passive"))
    )
    (net (code "9") (name "/COM2") (class "Default")
      (node (ref "LCD1") (pin "3") (pinfunction "COM2_3") (pintype "passive"))
      (node (ref "U9") (pin "55") (pinfunction "PA12/COM2_55") (pintype "passive"))
    )
    (net (code "10") (name "/COM3") (class "Default")
      (node (ref "LCD1") (pin "4") (pinfunction "COM3_4") (pintype "passive"))
      (node (ref "U9") (pin "62") (pinfunction "PC9/BOOT0/COM3_62") (pintype "passive"))
    )
    (net (code "11") (name "/DOUT") (class "Default")
      (node (ref "U9") (pin "79") (pinfunction "PE4/LPUART1_TX_79") (pintype "passive"))
    )
    (net (code "12") (name "/ESAM_CLK") (class "Default")
      (node (ref "U9") (pin "75") (pinfunction "PD2/LPTIM1_IN1_75") (pintype "passive"))
    )
    (net (code "13") (name "/ESAM_POW") (class "Default")
      (node (ref "U9") (pin "78") (pinfunction "PD5/USART4_RX/SEG27_78") (pintype "passive"))
    )
    (net (code "14") (name "/ESAM_RST") (class "Default")
      (node (ref "U9") (pin "74") (pinfunction "PE3/USART1_RX_74") (pintype "passive"))
    )
    (net (code "15") (name "/ESAM_SDA") (class "Default")
      (node (ref "U9") (pin "76") (pinfunction "PD3/USART1_TX/SEG25/USART2_TX_76") (pintype "passive"))
    )
    (net (code "16") (name "/FLASH_CLK") (class "Default")
      (node (ref "U10") (pin "6") (pinfunction "SCK_6") (pintype "passive"))
      (node (ref "U9") (pin "65") (pinfunction "PC11/SEG2_65") (pintype "passive"))
    )
    (net (code "17") (name "/FLASH_CS") (class "Default")
      (node (ref "U10") (pin "1") (pinfunction "CE#_1") (pintype "passive"))
      (node (ref "U9") (pin "67") (pinfunction "PB4/SEG4_67") (pintype "passive"))
    )
    (net (code "18") (name "/FLASH_CTL") (class "Default")
      (node (ref "R49") (pin "1") (pinfunction "1_1") (pintype "passive"))
      (node (ref "U9") (pin "73") (pinfunction "PE2/TIM1_CH2N_73") (pintype "passive"))
    )
    (net (code "19") (name "/FLASH_MISO") (class "Default")
      (node (ref "U10") (pin "2") (pinfunction "SO_2") (pintype "passive"))
      (node (ref "U9") (pin "66") (pinfunction "PB3/SEG3_66") (pintype "passive"))
    )
    (net (code "20") (name "/FLASH_MOSI") (class "Default")
      (node (ref "U10") (pin "5") (pinfunction "SI_5") (pintype "passive"))
      (node (ref "U9") (pin "64") (pinfunction "PC10/SEG1_64") (pintype "passive"))
    )
    (net (code "21") (name "/GPRS_POWER") (class "Default")
      (node (ref "U9") (pin "25") (pinfunction "PC5/SEG23/USART3_TX_25") (pintype "passive"))
    )
    (net (code "22") (name "/GPRS_RST") (class "Default")
      (node (ref "U9") (pin "24") (pinfunction "PC4/USART1_RX/SEG22_24") (pintype "passive"))
    )
    (net (code "23") (name "/HALL1_INTP6") (class "Default")
      (node (ref "C29") (pin "1") (pinfunction "1_1") (pintype "passive"))
      (node (ref "C56") (pin "1") (pinfunction "1_1") (pintype "passive"))
      (node (ref "U7") (pin "2") (pinfunction "OUT_2") (pintype "passive"))
      (node (ref "U9") (pin "71") (pinfunction "PB8/SEG8_71") (pintype "passive"))
    )
    (net (code "24") (name "/HALL2_INTP7") (class "Default")
      (node (ref "C30") (pin "1") (pinfunction "1_1") (pintype "passive"))
      (node (ref "C50") (pin "1") (pinfunction "1_1") (pintype "passive"))
      (node (ref "R3") (pin "1") (pinfunction "1_1") (pintype "passive"))
      (node (ref "U6") (pin "2") (pinfunction "OUT_2") (pintype "passive"))
      (node (ref "U9") (pin "72") (pinfunction "PB9/SEG9_72") (pintype "passive"))
    )
    (net (code "25") (name "/IN1") (class "Default")
      (node (ref "D10") (pin "3") (pinfunction "C_3") (pintype "passive"))
      (node (ref "P5") (pin "1") (pinfunction "1_1") (pintype "passive"))
      (node (ref "TVS2") (pin "2") (pinfunction "2_2") (pintype "passive"))
    )
    (net (code "26") (name "/IN2") (class "Default")
      (node (ref "FB2") (pin "2") (pinfunction "2_2") (pintype "passive"))
      (node (ref "P5") (pin "2") (pinfunction "2_2") (pintype "passive"))
    )
    (net (code "27") (name "/IrDA_CTL") (class "Default")
      (node (ref "R27") (pin "1") (pinfunction "1_1") (pintype "passive"))
      (node (ref "U9") (pin "68") (pinfunction "PB5/SEG5/WKUP4_68") (pintype "passive"))
    )
    (net (code "28") (name "/IrDA_POW") (class "Default")
      (node (ref "D5") (pin "1") (pinfunction "A_1") (pintype "passive"))
      (node (ref "D6") (pin "2") (pinfunction "K_2") (pintype "passive"))
      (node (ref "Q7") (pin "3") (pinfunction "C_3") (pintype "passive"))
      (node (ref "R29") (pin "1") (pinfunction "1_1") (pintype "passive"))
      (node (ref "R34") (pin "2") (pinfunction "2_2") (pintype "passive"))
    )
    (net (code "29") (name "/IrDA_RxD1") (class "Default")
      (node (ref "C26") (pin "1") (pinfunction "1_1") (pintype "passive"))
      (node (ref "Q10") (pin "3") (pinfunction "C_3") (pintype "passive"))
      (node (ref "R29") (pin "2") (pinfunction "2_2") (pintype "passive"))
      (node (ref "R37") (pin "2") (pinfunction "2_2") (pintype "passive"))
      (node (ref "U9") (pin "70") (pinfunction "PB7/USART2_RX/SEG8_70") (pintype "passive"))
    )
    (net (code "30") (name "/IrDA_TxD1") (class "Default")
      (node (ref "R34") (pin "1") (pinfunction "1_1") (pintype "passive"))
      (node (ref "R36") (pin "2") (pinfunction "2_2") (pintype "passive"))
      (node (ref "R40") (pin "1") (pinfunction "1_1") (pintype "passive"))
      (node (ref "U9") (pin "69") (pinfunction "PB6/USART2_TX/SEG6_69") (pintype "passive"))
    )
    (net (code "31") (name "/Key_INTP0") (class "Default")
      (node (ref "C31") (pin "1") (pinfunction "1_1") (pintype "passive"))
      (node (ref "S1") (pin "1") (pinfunction "1_1") (pintype "passive"))
      (node (ref "U9") (pin "5") (pinfunction "PC12/TAMP_IN2_5") (pintype "passive"))
    )
    (net (code "32") (name "/LED") (class "Default")
      (node (ref "R7") (pin "1") (pinfunction "1_1") (pintype "passive"))
      (node (ref "U9") (pin "6") (pinfunction "PC13/WKUP1/TAMP_IN1/TIM1_BKIN_6") (pintype "passive"))
    )
    (net (code "33") (name "/MCU_RxD0") (class "Default")
      (node (ref "U9") (pin "31") (pinfunction "PB0/ADC_IN7/USART3_RX_31") (pintype "passive"))
    )
    (net (code "34") (name "/MCU_TxD0") (class "Default")
      (node (ref "U9") (pin "33") (pinfunction "PB2/ADC_IN9/USART3_TX_33") (pintype "passive"))
    )
    (net (code "35") (name "/OPEN") (class "Default")
      (node (ref "U9") (pin "36") (pinfunction "PD12/LPTIM1_IN1_36") (pintype "passive"))
    )
    (net (code "36") (name "/PWR") (class "Default")
      (node (ref "U9") (pin "16") (pinfunction "PF1/HXTAL_OUT_16") (pintype "passive"))
    )
    (net (code "37") (name "/PWR_CTL") (class "Default")
      (node (ref "U9") (pin "18") (pinfunction "PC1/SEG19/LPUART1_RX_18") (pintype "passive"))
    )
    (net (code "38") (name "/RST") (class "Default")
      (node (ref "C43") (pin "2") (pinfunction "2_2") (pintype "passive"))
      (node (ref "R1") (pin "1") (pinfunction "1_1") (pintype "passive"))
      (node (ref "U9") (pin "14") (pinfunction "NRST_14") (pintype "passive"))
    )
    (net (code "39") (name "/RXD5") (class "Default")
      (node (ref "U9") (pin "1") (pinfunction "PD6/SEG36/USART4/RX_1") (pintype "passive"))
    )
    (net (code "40") (name "/RxD1") (class "Default")
      (node (ref "P9") (pin "1") (pinfunction "1_1") (pintype "passive"))
      (node (ref "TP22") (pin "1") (pinfunction "1_1") (pintype "passive"))
      (node (ref "U9") (pin "22") (pinfunction "PA3/ADC_IN2/LPUART1_RX_22") (pintype "passive"))
    )
    (net (code "41") (name "/S0") (class "Default")
      (node (ref "LCD1") (pin "5") (pinfunction "SEG0_5") (pintype "passive"))
      (node (ref "U9") (pin "63") (pinfunction "PA15/USART2_RX/SEG0_63") (pintype "passive"))
    )
    (net (code "42") (name "/S1") (class "Default")
      (node (ref "LCD1") (pin "6") (pinfunction "SEG1_6") (pintype "passive"))
      (node (ref "U9") (pin "59") (pinfunction "PE1/SEG35_59") (pintype "passive"))
    )
    (net (code "43") (name "/S2") (class "Default")
      (node (ref "LCD1") (pin "7") (pinfunction "SEG2_7") (pintype "passive"))
      (node (ref "U9") (pin "58") (pinfunction "PE0/SEG34_58") (pintype "passive"))
    )
    (net (code "44") (name "/S3") (class "Default")
      (node (ref "LCD1") (pin "8") (pinfunction "SEG3_8") (pintype "passive"))
      (node (ref "U9") (pin "57") (pinfunction "PD15/SEG33/USART1_TX/USART3_RX_57") (pintype "passive"))
    )
    (net (code "45") (name "/S4") (class "Default")
      (node (ref "LCD1") (pin "9") (pinfunction "SEG4_9") (pintype "passive"))
      (node (ref "U9") (pin "56") (pinfunction "PD14/USART1_RX/SEG32/USART3_TX_56") (pintype "passive"))
    )
    (net (code "46") (name "/S5") (class "Default")
      (node (ref "LCD1") (pin "10") (pinfunction "SEG5_10") (pintype "passive"))
      (node (ref "U9") (pin "49") (pinfunction "PD1/SEG31_49") (pintype "passive"))
    )
    (net (code "47") (name "/S6") (class "Default")
      (node (ref "LCD1") (pin "11") (pinfunction "SEG6_11") (pintype "passive"))
      (node (ref "U9") (pin "48") (pinfunction "PD0/SEG30_48") (pintype "passive"))
    )
    (net (code "48") (name "/S7") (class "Default")
      (node (ref "LCD1") (pin "12") (pinfunction "SEG7_12") (pintype "passive"))
      (node (ref "U9") (pin "47") (pinfunction "PC8/SEG29/USART3_TX_47") (pintype "passive"))
    )
    (net (code "49") (name "/S8") (class "Default")
      (node (ref "LCD1") (pin "13") (pinfunction "SEG8_13") (pintype "passive"))
      (node (ref "U9") (pin "46") (pinfunction "PC7/SEG28/USART3_RX_46") (pintype "passive"))
    )
    (net (code "50") (name "/S9") (class "Default")
      (node (ref "LCD1") (pin "14") (pinfunction "SEG9_14") (pintype "passive"))
      (node (ref "U9") (pin "45") (pinfunction "PA9/SEG17_45") (pintype "passive"))
    )
    (net (code "51") (name "/S10") (class "Default")
      (node (ref "LCD1") (pin "15") (pinfunction "SEG10_15") (pintype "passive"))
      (node (ref "U9") (pin "44") (pinfunction "PA8/SEG16_44") (pintype "passive"))
    )
    (net (code "52") (name "/S11") (class "Default")
      (node (ref "LCD1") (pin "16") (pinfunction "SEG11_16") (pintype "passive"))
      (node (ref "U9") (pin "43") (pinfunction "PB15/SEG15_43") (pintype "passive"))
    )
    (net (code "53") (name "/S12") (class "Default")
      (node (ref "LCD1") (pin "17") (pinfunction "SEG12_17") (pintype "passive"))
      (node (ref "U9") (pin "42") (pinfunction "PB14/SEG14_42") (pintype "passive"))
    )
    (net (code "54") (name "/S13") (class "Default")
      (node (ref "LCD1") (pin "18") (pinfunction "SEG13_18") (pintype "passive"))
      (node (ref "U9") (pin "41") (pinfunction "PB13/ADC_IN16/WKUP3/SEG13_41") (pintype "passive"))
    )
    (net (code "55") (name "/S14") (class "Default")
      (node (ref "LCD1") (pin "19") (pinfunction "SEG14_19") (pintype "passive"))
      (node (ref "U9") (pin "40") (pinfunction "PB12/ADC_IN15/SEG12_40") (pintype "passive"))
    )
    (net (code "56") (name "/S15") (class "Default")
      (node (ref "LCD1") (pin "20") (pinfunction "SEG15_20") (pintype "passive"))
      (node (ref "U9") (pin "39") (pinfunction "PB11/ADC_IN11/SEG11/USART3_RX/LPUART1_TX_39") (pintype "passive"))
    )
    (net (code "57") (name "/S16") (class "Default")
      (node (ref "LCD1") (pin "21") (pinfunction "SEG16_21") (pintype "passive"))
      (node (ref "U9") (pin "38") (pinfunction "PB10/ADC_IN10/SEG10/USART3_TX/LPUART1_RX_38") (pintype "passive"))
    )
    (net (code "58") (name "/S17") (class "Default")
      (node (ref "LCD1") (pin "22") (pinfunction "GEG17_22") (pintype "passive"))
      (node (ref "U9") (pin "30") (pinfunction "PA7/ADC_IN6/SEG43/COM4_30") (pintype "passive"))
    )
    (net (code "59") (name "/S18") (class "Default")
      (node (ref "LCD1") (pin "23") (pinfunction "GEG18_23") (pintype "passive"))
      (node (ref "U9") (pin "29") (pinfunction "PA6/ADC_IN5/SEG42/COM5_29") (pintype "passive"))
    )
    (net (code "60") (name "/S19") (class "Default")
      (node (ref "LCD1") (pin "24") (pinfunction "GEG19_24") (pintype "passive"))
      (node (ref "U9") (pin "28") (pinfunction "PA5/ADC_IN4/SEG41/COM6_28") (pintype "passive"))
    )
    (net (code "61") (name "/S20") (class "Default")
      (node (ref "LCD1") (pin "25") (pinfunction "GEG20_25") (pintype "passive"))
      (node (ref "U9") (pin "27") (pinfunction "PA4/ADC_IN3/SEG40/COM7_27") (pintype "passive"))
    )
    (net (code "62") (name "/SET") (class "Default")
      (node (ref "Q8") (pin "3") (pinfunction "C_3") (pintype "passive"))
      (node (ref "U9") (pin "4") (pinfunction "PD9/SEG39/I2C2_SDA_4") (pintype "passive"))
    )
    (net (code "63") (name "/SLEEP") (class "Default")
      (node (ref "U9") (pin "37") (pinfunction "PD13/USART2_RX/LPTIM1_IN2_37") (pintype "passive"))
    )
    (net (code "64") (name "/SWCLK") (class "Default")
      (node (ref "R21") (pin "1") (pinfunction "1_1") (pintype "passive"))
      (node (ref "U9") (pin "61") (pinfunction "PA14/SWCLK/USART1_TX/USART2_TX_61") (pintype "passive"))
    )
    (net (code "65") (name "/SWIO") (class "Default")
      (node (ref "R8") (pin "2") (pinfunction "2_2") (pintype "passive"))
      (node (ref "U9") (pin "60") (pinfunction "PA13/SWDIO/USART1_RX_60") (pintype "passive"))
    )
    (net (code "66") (name "/TXD5") (class "Default")
      (node (ref "U9") (pin "2") (pinfunction "PD7/SEG37/USART4_TX_2") (pintype "passive"))
    )
    (net (code "67") (name "/VDD_XS_CTL") (class "Default")
      (node (ref "U9") (pin "80") (pinfunction "PE5/LPUART1_RX_80") (pintype "passive"))
    )
    (net (code "68") (name "/VREF+") (class "Default")
      (node (ref "C38") (pin "1") (pinfunction "1_1") (pintype "passive"))
      (node (ref "C39") (pin "1") (pinfunction "1_1") (pintype "passive"))
      (node (ref "U9") (pin "13") (pinfunction "VREF+/PA0/USART4_TX/COMP1_OUT_13") (pintype "passive"))
    )
    (net (code "69") (name "/VRTC") (class "Default")
      (node (ref "U9") (pin "9") (pinfunction "VBAT_9") (pintype "passive"))
    )
    (net (code "70") (name "/Vin_ADC") (class "Default")
      (node (ref "U9") (pin "20") (pinfunction "PA1/ADC_IN0/USART1_RX/USART4_RX_20") (pintype "passive"))
    )
    (net (code "71") (name "/WY_POW") (class "Default")
      (node (ref "C33") (pin "2") (pinfunction "2_2") (pintype "passive"))
      (node (ref "C64") (pin "2") (pinfunction "2_2") (pintype "passive"))
      (node (ref "P6") (pin "1") (pinfunction "1_1") (pintype "passive"))
      (node (ref "R43") (pin "1") (pinfunction "1_1") (pintype "passive"))
      (node (ref "R46") (pin "2") (pinfunction "2_2") (pintype "passive"))
      (node (ref "R97") (pin "2") (pinfunction "2_2") (pintype "passive"))
      (node (ref "TP9") (pin "1") (pinfunction "1_1") (pintype "passive"))
      (node (ref "U20") (pin "1") (pinfunction "VDDIO_1") (pintype "passive"))
      (node (ref "U20") (pin "3") (pinfunction "VDD_3") (pintype "passive"))
      (node (ref "U9") (pin "26") (pinfunction "PC6/SEG24/USART3_RX_26") (pintype "passive"))
    )
    (net (code "72") (name "/WY_SCL") (class "Default")
      (node (ref "C35") (pin "1") (pinfunction "1_1") (pintype "passive"))
      (node (ref "P7") (pin "1") (pinfunction "1_1") (pintype "passive"))
      (node (ref "R46") (pin "1") (pinfunction "1_1") (pintype "passive"))
      (node (ref "TP11") (pin "1") (pinfunction "1_1") (pintype "passive"))
      (node (ref "U20") (pin "5") (pinfunction "SCL_5") (pintype "passive"))
      (node (ref "U9") (pin "34") (pinfunction "PD10/ADC_IN17_34") (pintype "passive"))
    )
    (net (code "73") (name "/WY_SDA") (class "Default")
      (node (ref "C46") (pin "1") (pinfunction "1_1") (pintype "passive"))
      (node (ref "P6") (pin "2") (pinfunction "2_2") (pintype "passive"))
      (node (ref "R43") (pin "2") (pinfunction "2_2") (pintype "passive"))
      (node (ref "TP10") (pin "1") (pinfunction "1_1") (pintype "passive"))
      (node (ref "U20") (pin "6") (pinfunction "SDA_6") (pintype "passive"))
      (node (ref "U9") (pin "32") (pinfunction "PB1/ADC_IN8_32") (pintype "passive"))
    )
    (net (code "74") (name "/X1") (class "Default")
      (node (ref "R62") (pin "1") (pinfunction "1_1") (pintype "passive"))
      (node (ref "S2") (pin "1") (pintype "passive"))
      (node (ref "U9") (pin "23") (pinfunction "PC3/USART1_TX/SEG21_23") (pintype "passive"))
    )
    (net (code "75") (name "/XS_RST") (class "Default")
      (node (ref "U9") (pin "77") (pinfunction "PD4/USART4_TX/SEG26/USART2_RX_77") (pintype "passive"))
    )
    (net (code "76") (name "/XT1") (class "Default")
      (node (ref "C42") (pin "1") (pinfunction "1_1") (pintype "passive"))
      (node (ref "U9") (pin "8") (pinfunction "PC15/LXTAL_OUT_8") (pintype "passive"))
      (node (ref "Y1") (pin "1") (pinfunction "1_1") (pintype "passive"))
    )
    (net (code "77") (name "/XT2") (class "Default")
      (node (ref "C41") (pin "2") (pinfunction "2_2") (pintype "passive"))
      (node (ref "U9") (pin "7") (pinfunction "PC14/LXTAL_IN_7") (pintype "passive"))
      (node (ref "Y1") (pin "2") (pinfunction "2_2") (pintype "passive"))
    )
    (net (code "78") (name "3.3V") (class "Default")
      (node (ref "C27") (pin "1") (pinfunction "1_1") (pintype "passive"))
      (node (ref "C28") (pin "1") (pinfunction "1_1") (pintype "passive"))
      (node (ref "C48") (pin "1") (pinfunction "1_1") (pintype "passive"))
      (node (ref "C59") (pin "1") (pinfunction "1_1") (pintype "passive"))
      (node (ref "C60") (pin "1") (pinfunction "1_1") (pintype "passive"))
      (node (ref "C62") (pin "2") (pinfunction "2_2") (pintype "passive"))
      (node (ref "C63") (pin "2") (pinfunction "2_2") (pintype "passive"))
      (node (ref "D7") (pin "1") (pinfunction "1_1") (pintype "passive"))
      (node (ref "J2") (pin "5") (pinfunction "5_5") (pintype "passive"))
      (node (ref "Q11") (pin "2") (pinfunction "E_2") (pintype "passive"))
      (node (ref "Q12") (pin "2") (pinfunction "E_2") (pintype "passive"))
      (node (ref "Q7") (pin "2") (pinfunction "E_2") (pintype "passive"))
      (node (ref "R42") (pin "2") (pinfunction "2_2") (pintype "passive"))
      (node (ref "R62") (pin "2") (pinfunction "2_2") (pintype "passive"))
      (node (ref "U11") (pin "1") (pinfunction "VDD_1") (pintype "passive"))
      (node (ref "U6") (pin "1") (pinfunction "VDD_1") (pintype "passive"))
      (node (ref "U7") (pin "1") (pinfunction "VDD_1") (pintype "passive"))
      (node (ref "U9") (pin "12") (pinfunction "VDD/VDDA_12") (pintype "passive"))
      (node (ref "U9") (pin "50") (pinfunction "VDD/VDDA_50") (pintype "passive"))
    )
    (net (code "79") (name "GD_PWR") (class "Default")
      (node (ref "C45") (pin "1") (pinfunction "1_1") (pintype "passive"))
      (node (ref "P9") (pin "3") (pinfunction "3_3") (pintype "passive"))
      (node (ref "Q11") (pin "3") (pinfunction "C_3") (pintype "passive"))
      (node (ref "TP19") (pin "1") (pinfunction "1_1") (pintype "passive"))
    )
    (net (code "80") (name "GND") (class "Default")
      (node (ref "C26") (pin "2") (pinfunction "2_2") (pintype "passive"))
      (node (ref "C27") (pin "2") (pinfunction "2_2") (pintype "passive"))
      (node (ref "C28") (pin "2") (pinfunction "2_2") (pintype "passive"))
      (node (ref "C29") (pin "2") (pinfunction "2_2") (pintype "passive"))
      (node (ref "C30") (pin "2") (pinfunction "2_2") (pintype "passive"))
      (node (ref "C31") (pin "2") (pinfunction "2_2") (pintype "passive"))
      (node (ref "C32") (pin "2") (pinfunction "2_2") (pintype "passive"))
      (node (ref "C33") (pin "1") (pinfunction "1_1") (pintype "passive"))
      (node (ref "C35") (pin "2") (pinfunction "2_2") (pintype "passive"))
      (node (ref "C36") (pin "2") (pinfunction "2_2") (pintype "passive"))
      (node (ref "C38") (pin "2") (pinfunction "2_2") (pintype "passive"))
      (node (ref "C39") (pin "2") (pinfunction "2_2") (pintype "passive"))
      (node (ref "C41") (pin "1") (pinfunction "1_1") (pintype "passive"))
      (node (ref "C42") (pin "2") (pinfunction "2_2") (pintype "passive"))
      (node (ref "C43") (pin "1") (pinfunction "1_1") (pintype "passive"))
      (node (ref "C45") (pin "2") (pinfunction "2_2") (pintype "passive"))
      (node (ref "C46") (pin "2") (pinfunction "2_2") (pintype "passive"))
      (node (ref "C48") (pin "2") (pinfunction "2_2") (pintype "passive"))
      (node (ref "C49") (pin "2") (pinfunction "2_2") (pintype "passive"))
      (node (ref "C50") (pin "2") (pinfunction "2_2") (pintype "passive"))
      (node (ref "C53") (pin "1") (pinfunction "1_1") (pintype "passive"))
      (node (ref "C56") (pin "2") (pinfunction "2_2") (pintype "passive"))
      (node (ref "C59") (pin "2") (pinfunction "2_2") (pintype "passive"))
      (node (ref "C60") (pin "2") (pinfunction "2_2") (pintype "passive"))
      (node (ref "C61") (pin "1") (pinfunction "1_1") (pintype "passive"))
      (node (ref "C62") (pin "1") (pinfunction "1_1") (pintype "passive"))
      (node (ref "C63") (pin "1") (pinfunction "1_1") (pintype "passive"))
      (node (ref "C64") (pin "1") (pinfunction "1_1") (pintype "passive"))
      (node (ref "C65") (pin "2") (pinfunction "2_2") (pintype "passive"))
      (node (ref "C8") (pin "2") (pinfunction "2_2") (pintype "passive"))
      (node (ref "FB2") (pin "1") (pinfunction "1_1") (pintype "passive"))
      (node (ref "J1") (pin "1") (pinfunction "1_1") (pintype "passive"))
      (node (ref "J2") (pin "4") (pinfunction "4_4") (pintype "passive"))
      (node (ref "P7") (pin "2") (pinfunction "2_2") (pintype "passive"))
      (node (ref "P9") (pin "2") (pinfunction "2_2") (pintype "passive"))
      (node (ref "Q10") (pin "2") (pinfunction "E_2") (pintype "passive"))
      (node (ref "Q5") (pin "2") (pinfunction "E_2") (pintype "passive"))
      (node (ref "Q8") (pin "2") (pinfunction "E_2") (pintype "passive"))
      (node (ref "Q9") (pin "3") (pinfunction "C_3") (pintype "passive"))
      (node (ref "R38") (pin "1") (pinfunction "1_1") (pintype "passive"))
      (node (ref "R41") (pin "1") (pinfunction "1_1") (pintype "passive"))
      (node (ref "R96") (pin "1") (pinfunction "1_1") (pintype "passive"))
      (node (ref "S1") (pin "2") (pinfunction "2_2") (pintype "passive"))
      (node (ref "S2") (pin "2") (pintype "passive"))
      (node (ref "TP12") (pin "1") (pinfunction "1_1") (pintype "passive"))
      (node (ref "TVS2") (pin "1") (pinfunction "1_1") (pintype "passive"))
      (node (ref "U10") (pin "4") (pinfunction "VSS_4") (pintype "passive"))
      (node (ref "U11") (pin "3") (pinfunction "GND_3") (pintype "passive"))
      (node (ref "U20") (pin "2") (pinfunction "GND_2") (pintype "passive"))
      (node (ref "U6") (pin "3") (pinfunction "GND_3") (pintype "passive"))
      (node (ref "U7") (pin "3") (pinfunction "GND_3") (pintype "passive"))
      (node (ref "U9") (pin "11") (pinfunction "VSS/VSSA_11") (pintype "passive"))
      (node (ref "U9") (pin "51") (pinfunction "VSS/VSSA_51") (pintype "passive"))
    )
    (net (code "81") (name "Net-(B1-+)") (class "Default")
      (node (ref "B1") (pin "1") (pinfunction "+_1") (pintype "passive"))
      (node (ref "R42") (pin "1") (pinfunction "1_1") (pintype "passive"))
    )
    (net (code "82") (name "Net-(B1--)") (class "Default")
      (node (ref "B1") (pin "2") (pinfunction "-_2") (pintype "passive"))
      (node (ref "Q5") (pin "3") (pinfunction "C_3") (pintype "passive"))
    )
    (net (code "83") (name "Net-(D5-K)") (class "Default")
      (node (ref "D5") (pin "2") (pinfunction "K_2") (pintype "passive"))
      (node (ref "R35") (pin "2") (pinfunction "2_2") (pintype "passive"))
    )
    (net (code "84") (name "Net-(D6-A)") (class "Default")
      (node (ref "D6") (pin "1") (pinfunction "A_1") (pintype "passive"))
      (node (ref "R39") (pin "2") (pinfunction "2_2") (pintype "passive"))
    )
    (net (code "85") (name "Net-(D7-Pad2)") (class "Default")
      (node (ref "D7") (pin "2") (pinfunction "2_2") (pintype "passive"))
      (node (ref "R7") (pin "2") (pinfunction "2_2") (pintype "passive"))
    )
    (net (code "86") (name "Net-(D10-A-Pad1)") (class "Default")
      (node (ref "D10") (pin "1") (pinfunction "A_1") (pintype "passive"))
      (node (ref "D10") (pin "2") (pinfunction "A_2") (pintype "passive"))
      (node (ref "FB1") (pin "2") (pinfunction "2_2") (pintype "passive"))
    )
    (net (code "87") (name "Net-(J1-Pad2)") (class "Default")
      (node (ref "J1") (pin "2") (pinfunction "2_2") (pintype "passive"))
      (node (ref "R37") (pin "1") (pinfunction "1_1") (pintype "passive"))
    )
    (net (code "88") (name "Net-(J1-Pad3)") (class "Default")
      (node (ref "J1") (pin "3") (pinfunction "3_3") (pintype "passive"))
      (node (ref "R36") (pin "1") (pinfunction "1_1") (pintype "passive"))
    )
    (net (code "89") (name "Net-(J1-Pad4)") (class "Default")
      (node (ref "J1") (pin "4") (pinfunction "4_4") (pintype "passive"))
      (node (ref "R31") (pin "1") (pinfunction "1_1") (pintype "passive"))
    )
    (net (code "90") (name "Net-(J2-Pad1)") (class "Default")
      (node (ref "J2") (pin "1") (pinfunction "1_1") (pintype "passive"))
      (node (ref "R1") (pin "2") (pinfunction "2_2") (pintype "passive"))
    )
    (net (code "91") (name "Net-(J2-Pad2)") (class "Default")
      (node (ref "J2") (pin "2") (pinfunction "2_2") (pintype "passive"))
      (node (ref "R21") (pin "2") (pinfunction "2_2") (pintype "passive"))
    )
    (net (code "92") (name "Net-(J2-Pad3)") (class "Default")
      (node (ref "J2") (pin "3") (pinfunction "3_3") (pintype "passive"))
      (node (ref "R8") (pin "1") (pinfunction "1_1") (pintype "passive"))
    )
    (net (code "93") (name "Net-(Q5-B)") (class "Default")
      (node (ref "Q5") (pin "1") (pinfunction "B_1") (pintype "passive"))
      (node (ref "R47") (pin "2") (pinfunction "2_2") (pintype "passive"))
    )
    (net (code "94") (name "Net-(Q7-B)") (class "Default")
      (node (ref "Q7") (pin "1") (pinfunction "B_1") (pintype "passive"))
      (node (ref "R27") (pin "2") (pinfunction "2_2") (pintype "passive"))
    )
    (net (code "95") (name "Net-(Q8-B)") (class "Default")
      (node (ref "Q8") (pin "1") (pinfunction "B_1") (pintype "passive"))
      (node (ref "R31") (pin "2") (pinfunction "2_2") (pintype "passive"))
      (node (ref "R38") (pin "2") (pinfunction "2_2") (pintype "passive"))
    )
    (net (code "96") (name "Net-(Q9-B)") (class "Default")
      (node (ref "Q9") (pin "1") (pinfunction "B_1") (pintype "passive"))
      (node (ref "R40") (pin "2") (pinfunction "2_2") (pintype "passive"))
    )
    (net (code "97") (name "Net-(Q9-E)") (class "Default")
      (node (ref "Q9") (pin "2") (pinfunction "E_2") (pintype "passive"))
      (node (ref "R35") (pin "1") (pinfunction "1_1") (pintype "passive"))
    )
    (net (code "98") (name "Net-(Q10-B)") (class "Default")
      (node (ref "C32") (pin "1") (pinfunction "1_1") (pintype "passive"))
      (node (ref "Q10") (pin "1") (pinfunction "B_1") (pintype "passive"))
      (node (ref "R39") (pin "1") (pinfunction "1_1") (pintype "passive"))
      (node (ref "R41") (pin "2") (pinfunction "2_2") (pintype "passive"))
    )
    (net (code "99") (name "Net-(Q11-B)") (class "Default")
      (node (ref "Q11") (pin "1") (pinfunction "B_1") (pintype "passive"))
      (node (ref "R3") (pin "2") (pinfunction "2_2") (pintype "passive"))
    )
    (net (code "100") (name "Net-(Q12-B)") (class "Default")
      (node (ref "Q12") (pin "1") (pinfunction "B_1") (pintype "passive"))
      (node (ref "R49") (pin "2") (pinfunction "2_2") (pintype "passive"))
    )
    (net (code "101") (name "Net-(Q12-C)") (class "Default")
      (node (ref "C36") (pin "1") (pinfunction "1_1") (pintype "passive"))
      (node (ref "Q12") (pin "3") (pinfunction "C_3") (pintype "passive"))
      (node (ref "U10") (pin "3") (pinfunction "WP#_3") (pintype "passive"))
      (node (ref "U10") (pin "7") (pinfunction "HOLD#_7") (pintype "passive"))
      (node (ref "U10") (pin "8") (pinfunction "VDD_8") (pintype "passive"))
    )
    (net (code "102") (name "Net-(U9-VCORE)") (class "Default")
      (node (ref "C53") (pin "2") (pinfunction "2_2") (pintype "passive"))
      (node (ref "C61") (pin "2") (pinfunction "2_2") (pintype "passive"))
      (node (ref "U9") (pin "10") (pinfunction "VCORE_10") (pintype "passive"))
    )
    (net (code "103") (name "Net-(U9-VLCD)") (class "Default")
      (node (ref "C65") (pin "1") (pinfunction "1_1") (pintype "passive"))
      (node (ref "U9") (pin "52") (pinfunction "VLCD_52") (pintype "passive"))
    )
    (net (code "104") (name "Net-(U20-SDO)") (class "Default")
      (node (ref "R96") (pin "2") (pinfunction "2_2") (pintype "passive"))
      (node (ref "R97") (pin "1") (pinfunction "1_1") (pintype "passive"))
      (node (ref "U20") (pin "8") (pinfunction "SDO_8") (pintype "passive"))
    )
    (net (code "105") (name "unconnected-(U20-CSB-Pad7)") (class "Default")
      (node (ref "U20") (pin "7") (pinfunction "CSB_7") (pintype "passive"))
    )
    (net (code "106") (name "unconnected-(U20-NC-Pad4)") (class "Default")
      (node (ref "U20") (pin "4") (pinfunction "NC_4") (pintype "passive+no_connect"))
    )
  )
)
